# Controlador_SCH.net
KiCad netlist of a schematic drawn in Altium Designer
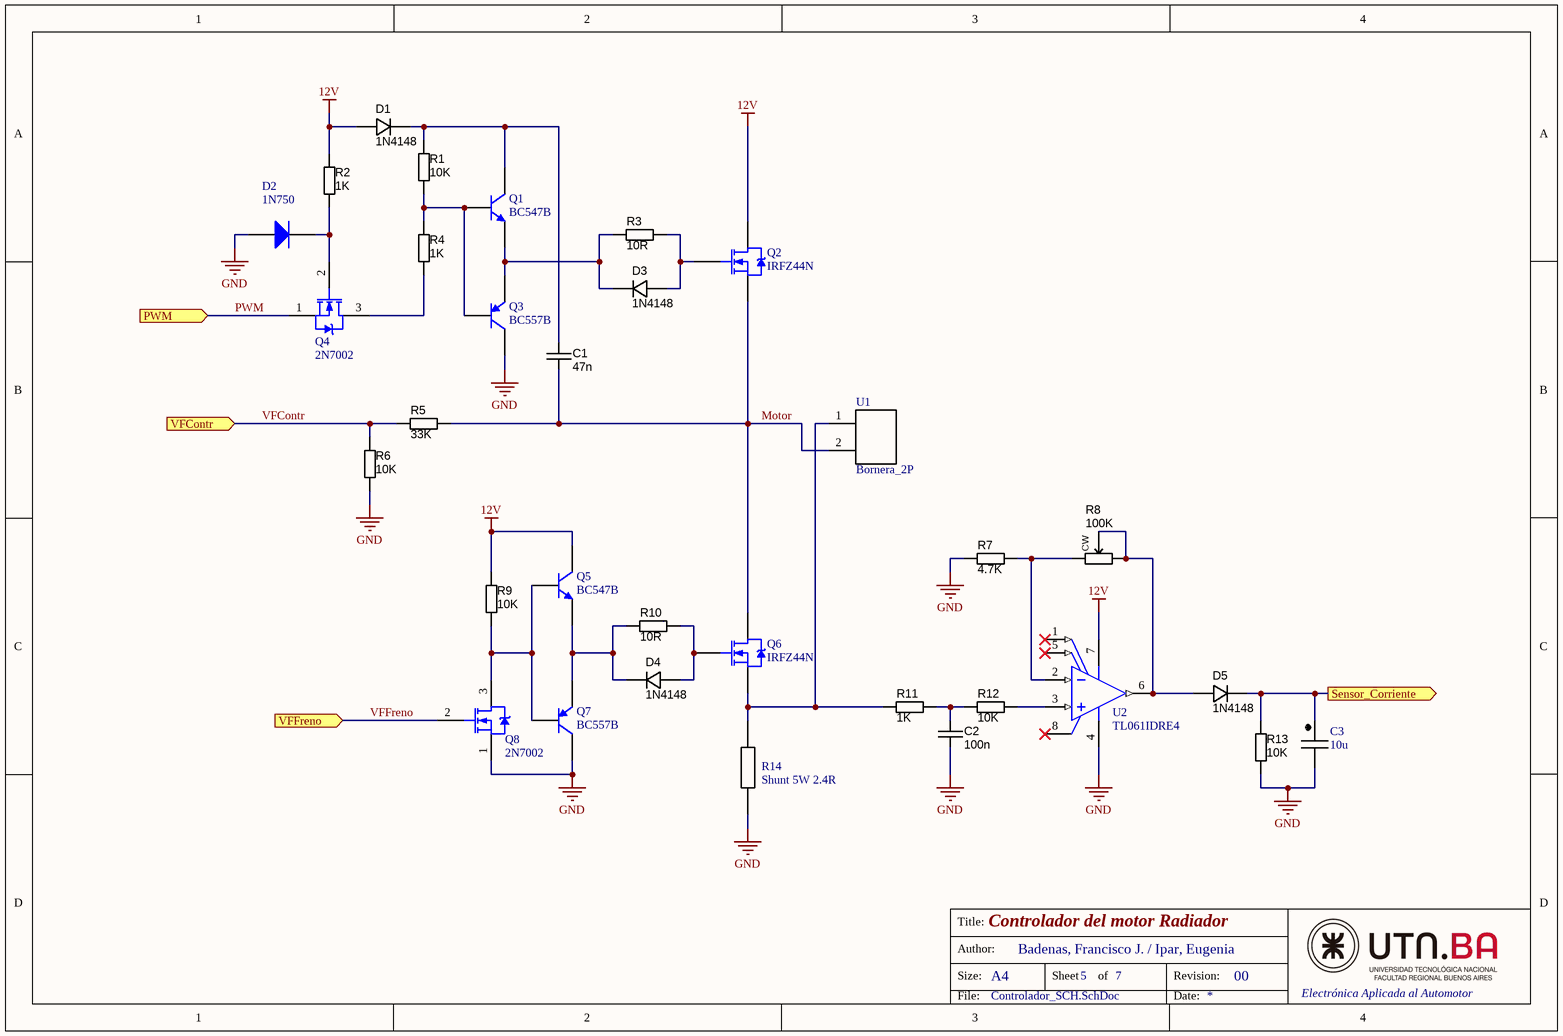
[diagram p0: Controlador_SCH.SchDoc]

(export (version "E")
  (design (tool "Eeschema 10.0.6"))
  (components
    (comp (ref "C1")
      (value "47n")
      (footprint "CAPC1608X90N")
      (description "Capacitor SMD Cer 47nF 10% 50V X7R 0603")
      (fields (field (name "TOLERANCE") "±10%"))
      (libsource (lib "PBL - Capacitors") (part "CAPC_47n_0603_X7R_50V_10%"))
    )
    (comp (ref "C2")
      (value "100n")
      (footprint "CAPC1608X90N")
      (description "Capacitor SMD Cer 100nF 10% 50V X7R 0603")
      (fields (field (name "TOLERANCE") "±10%"))
      (libsource (lib "PBL - Capacitors") (part "CAPC_47n_0603_X7R_50V_10%"))
    )
    (comp (ref "C3")
      (value "10u")
      (footprint "CAP_Elec_5x5.7")
      (libsource (lib "Ampli_Lib_Sch") (part "CAP_Elec_4x4"))
    )
    (comp (ref "D1")
      (value "1N4148")
      (footprint "SOD523F")
      (description "Diode 1N4148 SMD SOD-523F")
      (libsource (lib "PBL - Diodes") (part "DIODE_1N4148_200mA_SOD523F"))
    )
    (comp (ref "D2")
      (value "1N750")
      (footprint "DO-35")
      (description "Diodo 1N750 THD DO-35")
      (fields (field (name "PUBLISHER") "Altium Limited"))
      (libsource (lib "Miscellaneous Devices") (part "Diode 1N914"))
    )
    (comp (ref "D3")
      (value "1N4148")
      (footprint "SOD523F")
      (description "Diode 1N4148 SMD SOD-523F")
      (libsource (lib "PBL - Diodes") (part "DIODE_1N4148_200mA_SOD523F"))
    )
    (comp (ref "D4")
      (value "1N4148")
      (footprint "SOD523F")
      (description "Diode 1N4148 SMD SOD-523F")
      (libsource (lib "PBL - Diodes") (part "DIODE_1N4148_200mA_SOD523F"))
    )
    (comp (ref "D5")
      (value "1N4148")
      (footprint "SOD523F")
      (description "Diode 1N4148 SMD SOD-523F")
      (libsource (lib "PBL - Diodes") (part "DIODE_1N4148_200mA_SOD523F"))
    )
    (comp (ref "Q1")
      (value "BC547B")
      (footprint "TO-92A")
      (description "NPN General Purpose Amplifier")
      (fields (field (name "PUBLISHER") "Altium Limited"))
      (libsource (lib "Miscellaneous Devices") (part "2N3904"))
    )
    (comp (ref "Q2")
      (value "IRFZ44N")
      (footprint "TO-220AB")
      (description "N-Channel Power MOSFET")
      (fields (field (name "PUBLISHER") "Altium Limited"))
      (libsource (lib "Miscellaneous Devices") (part "NMOS-2"))
    )
    (comp (ref "Q3")
      (value "BC557B")
      (footprint "TO-92A")
      (description "PNP General Purpose Amplifier")
      (fields (field (name "PUBLISHER") "Altium Limited"))
      (libsource (lib "Miscellaneous Devices") (part "2N3906"))
    )
    (comp (ref "Q4")
      (value "2N7002")
      (footprint "ONSC-TO-92-3-29-11_AM_BL")
      (description "Small Signal MOSFET, 200 mA, 60 V, N-Channel, 3-Pin TO-92, Pb-Free, Fan-Fold")
      (fields (field (name "PARTNUMBER") "2N7000RLRPG") (field (name "MANUFACTURER") "On Semiconductor"))
      (libsource (lib "Altium Content Vault") (part "CMP-1058-00948-1"))
    )
    (comp (ref "Q5")
      (value "BC547B")
      (footprint "TO-92A")
      (description "NPN General Purpose Amplifier")
      (fields (field (name "PUBLISHER") "Altium Limited"))
      (libsource (lib "Miscellaneous Devices") (part "2N3904"))
    )
    (comp (ref "Q6")
      (value "IRFZ44N")
      (footprint "TO-220AB")
      (description "N-Channel Power MOSFET")
      (fields (field (name "PUBLISHER") "Altium Limited"))
      (libsource (lib "Miscellaneous Devices") (part "NMOS-2"))
    )
    (comp (ref "Q7")
      (value "BC557B")
      (footprint "TO-92A")
      (description "PNP General Purpose Amplifier")
      (fields (field (name "PUBLISHER") "Altium Limited"))
      (libsource (lib "Miscellaneous Devices") (part "2N3906"))
    )
    (comp (ref "Q8")
      (value "2N7002")
      (footprint "ONSC-TO-92-3-29-11_AM_BL")
      (description "Small Signal MOSFET, 200 mA, 60 V, N-Channel, 3-Pin TO-92, Pb-Free, Fan-Fold")
      (fields (field (name "PARTNUMBER") "2N7000RLRPG") (field (name "MANUFACTURER") "On Semiconductor"))
      (libsource (lib "Altium Content Vault") (part "CMP-1058-00948-1"))
    )
    (comp (ref "R1")
      (value "10K")
      (footprint "RESC1608N_ZERO")
      (description "Resistor SMD 0603 10K 5%")
      (fields (field (name "TOLERANCE") "±5%"))
      (libsource (lib "PBL - Resistors") (part "RES_0R_0603"))
    )
    (comp (ref "R2")
      (value "1K")
      (footprint "RESC1608N_ZERO")
      (description "Resistor SMD 0603 1K 5%")
      (fields (field (name "TOLERANCE") "±5%"))
      (libsource (lib "PBL - Resistors") (part "RES_0R_0603"))
    )
    (comp (ref "R3")
      (value "10R")
      (footprint "RESC1608N_ZERO")
      (description "Resistor SMD 0603 10 Ohm 5%")
      (fields (field (name "TOLERANCE") "±5%"))
      (libsource (lib "") (part "RES_0R_0603_2"))
    )
    (comp (ref "R4")
      (value "1K")
      (footprint "RESC1608N_ZERO")
      (description "Resistor SMD 0603 1K 5%")
      (fields (field (name "TOLERANCE") "±5%"))
      (libsource (lib "PBL - Resistors") (part "RES_0R_0603"))
    )
    (comp (ref "R5")
      (value "33K")
      (footprint "RESC1608N_ZERO")
      (description "Resistor SMD 0603 33K 5%")
      (fields (field (name "TOLERANCE") "±5%"))
      (libsource (lib "") (part "RES_0R_0603_2"))
    )
    (comp (ref "R6")
      (value "10K")
      (footprint "RESC1608N_ZERO")
      (description "Resistor SMD 0603 10K 5%")
      (fields (field (name "TOLERANCE") "±5%"))
      (libsource (lib "PBL - Resistors") (part "RES_0R_0603"))
    )
    (comp (ref "R7")
      (value "4.7K")
      (footprint "RESC1608N_ZERO")
      (description "Resistor SMD 0603 4.7K 5%")
      (fields (field (name "TOLERANCE") "±5%"))
      (libsource (lib "") (part "RES_0R_0603_2"))
    )
    (comp (ref "R8")
      (value "100K")
      (footprint "TRIMPOT_THT_PV36X")
      (description "Trimmer THD 10K 500mW 25-turn")
      (fields (field (name "TOLERANCE") "±10%") (field (name "Comment") "Multivuelta 10K"))
      (libsource (lib "PBL - Resistors") (part "RES_TRIMMER_10K_25T_THT"))
    )
    (comp (ref "R9")
      (value "10K")
      (footprint "RESC1608N_ZERO")
      (description "Resistor SMD 0603 10K 5%")
      (fields (field (name "TOLERANCE") "±5%"))
      (libsource (lib "PBL - Resistors") (part "RES_0R_0603"))
    )
    (comp (ref "R10")
      (value "10R")
      (footprint "RESC1608N_ZERO")
      (description "Resistor SMD 0603 10 Ohm 5%")
      (fields (field (name "TOLERANCE") "±5%"))
      (libsource (lib "") (part "RES_0R_0603_2"))
    )
    (comp (ref "R11")
      (value "1K")
      (footprint "RESC1608N_ZERO")
      (description "Resistor SMD 0603 1K 5%")
      (fields (field (name "TOLERANCE") "±5%"))
      (libsource (lib "") (part "RES_0R_0603_2"))
    )
    (comp (ref "R12")
      (value "10K")
      (footprint "RESC1608N_ZERO")
      (description "Resistor SMD 0603 10K 5%")
      (fields (field (name "TOLERANCE") "±5%"))
      (libsource (lib "") (part "RES_0R_0603_2"))
    )
    (comp (ref "R13")
      (value "10K")
      (footprint "RESC1608N_ZERO")
      (description "Resistor SMD 0603 10K 5%")
      (fields (field (name "TOLERANCE") "±5%"))
      (libsource (lib "") (part "RES_0R_0603_1"))
    )
    (comp (ref "R14")
      (value "Shunt 5W 2.4R")
      (footprint "Resistor")
      (description "Resistencia de Alambre 5W 2.4 Ohm")
      (libsource (lib "Ampli_Lib_Sch") (part "Resistor 10W"))
    )
    (comp (ref "U1")
      (value "Bornera_2P")
      (footprint "Bornera")
      (libsource (lib "Ampli_Lib_Sch") (part "Bornera_2P"))
    )
    (comp (ref "U2")
      (value "TL061IDRE4")
      (footprint "TI-D8_N")
      (fields (field (name "MANUFACTURER") "Texas Instruments"))
      (libsource (lib "Altium Content Vault") (part "CMP-0017-00647-1"))
    )
  )
  (nets
    (net (code "1") (name "/Motor") (class "Default")
      (node (ref "C1") (pin "2") (pintype "passive"))
      (node (ref "Q2") (pin "3") (pinfunction "S_3") (pintype "passive"))
      (node (ref "Q6") (pin "2") (pinfunction "D_2") (pintype "passive"))
      (node (ref "R5") (pin "2") (pinfunction "2_2") (pintype "passive"))
      (node (ref "U1") (pin "2") (pinfunction "2_2") (pintype "passive"))
    )
    (net (code "2") (name "/PWM") (class "Default")
      (node (ref "Q4") (pin "1") (pinfunction "S_1") (pintype "passive"))
    )
    (net (code "3") (name "/Sensor_Corriente") (class "Default")
      (node (ref "C3") (pin "1") (pinfunction "1_1") (pintype "passive"))
      (node (ref "D5") (pin "K") (pinfunction "K_K") (pintype "passive"))
      (node (ref "R13") (pin "2") (pinfunction "2_2") (pintype "passive"))
    )
    (net (code "4") (name "/VFContr") (class "Default")
      (node (ref "R5") (pin "1") (pinfunction "1_1") (pintype "passive"))
      (node (ref "R6") (pin "1") (pinfunction "1_1") (pintype "passive"))
    )
    (net (code "5") (name "/VFFreno") (class "Default")
      (node (ref "Q8") (pin "2") (pinfunction "G_2") (pintype "passive"))
    )
    (net (code "6") (name "12V") (class "Default")
      (node (ref "D1") (pin "A") (pinfunction "A_A") (pintype "passive"))
      (node (ref "Q2") (pin "2") (pinfunction "D_2") (pintype "passive"))
      (node (ref "Q5") (pin "3") (pinfunction "C_3") (pintype "passive"))
      (node (ref "R2") (pin "1") (pinfunction "1_1") (pintype "passive"))
      (node (ref "R9") (pin "1") (pinfunction "1_1") (pintype "passive"))
      (node (ref "U2") (pin "7") (pinfunction "VCC+_7") (pintype "power_in"))
    )
    (net (code "7") (name "GND") (class "Default")
      (node (ref "C2") (pin "2") (pintype "passive"))
      (node (ref "C3") (pin "2") (pinfunction "2_2") (pintype "passive"))
      (node (ref "D2") (pin "1") (pinfunction "A_1") (pintype "passive"))
      (node (ref "Q3") (pin "3") (pinfunction "C_3") (pintype "passive"))
      (node (ref "Q7") (pin "3") (pinfunction "C_3") (pintype "passive"))
      (node (ref "Q8") (pin "1") (pinfunction "S_1") (pintype "passive"))
      (node (ref "R13") (pin "1") (pinfunction "1_1") (pintype "passive"))
      (node (ref "R14") (pin "1") (pinfunction "1_1") (pintype "passive"))
      (node (ref "R6") (pin "2") (pinfunction "2_2") (pintype "passive"))
      (node (ref "R7") (pin "1") (pinfunction "1_1") (pintype "passive"))
      (node (ref "U2") (pin "4") (pinfunction "VCC-_4") (pintype "power_in"))
    )
    (net (code "8") (name "Net-(C2-Pad1)") (class "Default")
      (node (ref "C2") (pin "1") (pintype "passive"))
      (node (ref "R11") (pin "2") (pinfunction "2_2") (pintype "passive"))
      (node (ref "R12") (pin "1") (pinfunction "1_1") (pintype "passive"))
    )
    (net (code "9") (name "Net-(D2-K)") (class "Default")
      (node (ref "D2") (pin "2") (pinfunction "K_2") (pintype "passive"))
      (node (ref "Q4") (pin "2") (pinfunction "G_2") (pintype "passive"))
      (node (ref "R2") (pin "2") (pinfunction "2_2") (pintype "passive"))
    )
    (net (code "10") (name "Net-(Q1-B)") (class "Default")
      (node (ref "Q1") (pin "2") (pinfunction "B_2") (pintype "passive"))
      (node (ref "Q3") (pin "2") (pinfunction "B_2") (pintype "passive"))
      (node (ref "R1") (pin "2") (pinfunction "2_2") (pintype "passive"))
      (node (ref "R4") (pin "1") (pinfunction "1_1") (pintype "passive"))
    )
    (net (code "11") (name "Net-(Q1-C)") (class "Default")
      (node (ref "C1") (pin "1") (pintype "passive"))
      (node (ref "D1") (pin "K") (pinfunction "K_K") (pintype "passive"))
      (node (ref "Q1") (pin "3") (pinfunction "C_3") (pintype "passive"))
      (node (ref "R1") (pin "1") (pinfunction "1_1") (pintype "passive"))
    )
    (net (code "12") (name "Net-(Q1-E)") (class "Default")
      (node (ref "D3") (pin "K") (pinfunction "K_K") (pintype "passive"))
      (node (ref "Q1") (pin "1") (pinfunction "E_1") (pintype "passive"))
      (node (ref "Q3") (pin "1") (pinfunction "E_1") (pintype "passive"))
      (node (ref "R3") (pin "1") (pinfunction "1_1") (pintype "passive"))
    )
    (net (code "13") (name "Net-(Q2-G)") (class "Default")
      (node (ref "D3") (pin "A") (pinfunction "A_A") (pintype "passive"))
      (node (ref "Q2") (pin "1") (pinfunction "G_1") (pintype "passive"))
      (node (ref "R3") (pin "2") (pinfunction "2_2") (pintype "passive"))
    )
    (net (code "14") (name "Net-(Q4-D)") (class "Default")
      (node (ref "Q4") (pin "3") (pinfunction "D_3") (pintype "passive"))
      (node (ref "R4") (pin "2") (pinfunction "2_2") (pintype "passive"))
    )
    (net (code "15") (name "Net-(Q5-B)") (class "Default")
      (node (ref "Q5") (pin "2") (pinfunction "B_2") (pintype "passive"))
      (node (ref "Q7") (pin "2") (pinfunction "B_2") (pintype "passive"))
      (node (ref "Q8") (pin "3") (pinfunction "D_3") (pintype "passive"))
      (node (ref "R9") (pin "2") (pinfunction "2_2") (pintype "passive"))
    )
    (net (code "16") (name "Net-(Q5-E)") (class "Default")
      (node (ref "D4") (pin "K") (pinfunction "K_K") (pintype "passive"))
      (node (ref "Q5") (pin "1") (pinfunction "E_1") (pintype "passive"))
      (node (ref "Q7") (pin "1") (pinfunction "E_1") (pintype "passive"))
      (node (ref "R10") (pin "1") (pinfunction "1_1") (pintype "passive"))
    )
    (net (code "17") (name "Net-(Q6-G)") (class "Default")
      (node (ref "D4") (pin "A") (pinfunction "A_A") (pintype "passive"))
      (node (ref "Q6") (pin "1") (pinfunction "G_1") (pintype "passive"))
      (node (ref "R10") (pin "2") (pinfunction "2_2") (pintype "passive"))
    )
    (net (code "18") (name "Net-(Q6-S)") (class "Default")
      (node (ref "Q6") (pin "3") (pinfunction "S_3") (pintype "passive"))
      (node (ref "R11") (pin "1") (pinfunction "1_1") (pintype "passive"))
      (node (ref "R14") (pin "2") (pinfunction "2_2") (pintype "passive"))
      (node (ref "U1") (pin "1") (pinfunction "1_1") (pintype "passive"))
    )
    (net (code "19") (name "Net-(R8-1)") (class "Default")
      (node (ref "D5") (pin "A") (pinfunction "A_A") (pintype "passive"))
      (node (ref "R8") (pin "CCW") (pinfunction "1_CCW") (pintype "passive"))
      (node (ref "R8") (pin "W") (pinfunction "2_W") (pintype "passive"))
      (node (ref "U2") (pin "6") (pinfunction "OUT_6") (pintype "output"))
    )
    (net (code "20") (name "Net-(R8-3)") (class "Default")
      (node (ref "R7") (pin "2") (pinfunction "2_2") (pintype "passive"))
      (node (ref "R8") (pin "CW") (pinfunction "3_CW") (pintype "passive"))
      (node (ref "U2") (pin "2") (pinfunction "IN-_2") (pintype "input"))
    )
    (net (code "21") (name "Net-(U2-IN+)") (class "Default")
      (node (ref "R12") (pin "2") (pinfunction "2_2") (pintype "passive"))
      (node (ref "U2") (pin "3") (pinfunction "IN+_3") (pintype "input"))
    )
    (net (code "22") (name "unconnected-(U2-NC-Pad8)") (class "Default")
      (node (ref "U2") (pin "8") (pinfunction "NC_8") (pintype "passive+no_connect"))
    )
    (net (code "23") (name "unconnected-(U2-OFFSET_N1-Pad1)") (class "Default")
      (node (ref "U2") (pin "1") (pinfunction "OFFSET_N1_1") (pintype "input+no_connect"))
    )
    (net (code "24") (name "unconnected-(U2-OFFSET_N2-Pad5)") (class "Default")
      (node (ref "U2") (pin "5") (pinfunction "OFFSET_N2_5") (pintype "input+no_connect"))
    )
  )
)
